# ATMega32U4.net
KiCad netlist of a schematic drawn in Altium Designer
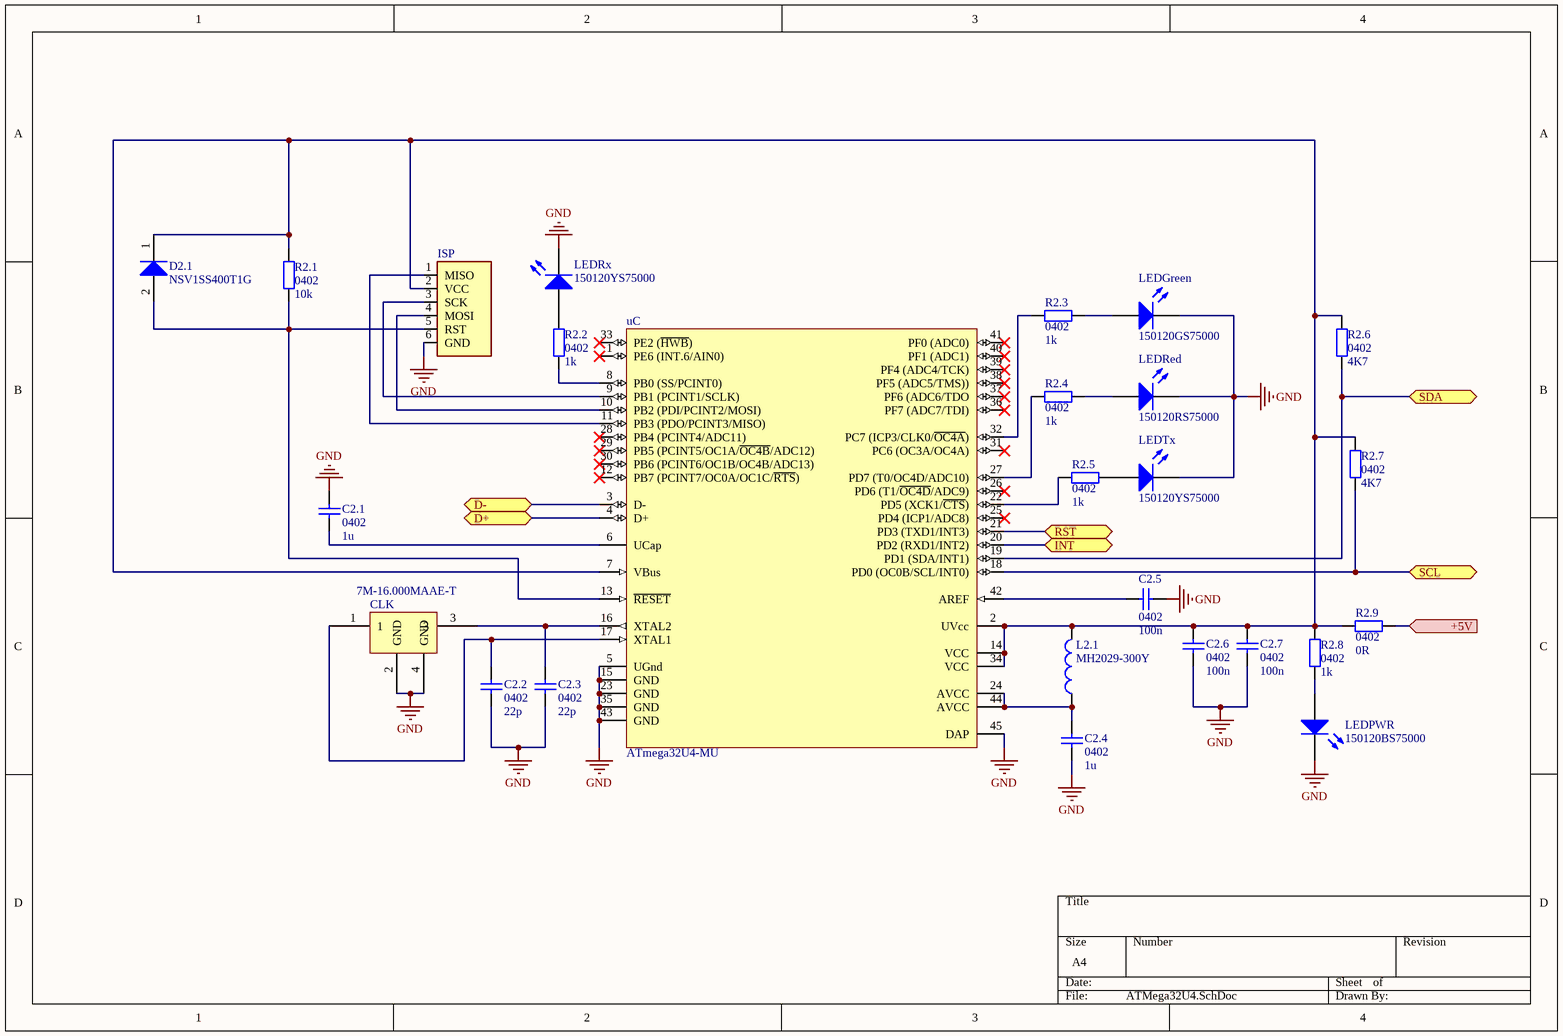
[diagram p0: ATMega32U4.SchDoc]

(export (version "E")
  (design (tool "Eeschema 10.0.6"))
  (components
    (comp (ref "C2.1")
      (value "0402")
      (footprint "C0402_M")
      (description "Capacitor")
      (fields
        (field (name "PART NUMBER") "C0402_X5R_1u_10V_WE")
        (field (name "ALTIUM_VALUE") "1u")
        (field (name "TOLERANCE") "±20%")
      )
      (libsource (lib "LTE_altium") (part "Cap"))
    )
    (comp (ref "C2.2")
      (value "0402")
      (footprint "C0402_M")
      (description "Capacitor")
      (fields
        (field (name "PART NUMBER") "C0402_NP0_22p_50V_WE")
        (field (name "ALTIUM_VALUE") "22p")
        (field (name "TOLERANCE") "±5%")
      )
      (libsource (lib "LTE_altium") (part "Cap"))
    )
    (comp (ref "C2.3")
      (value "0402")
      (footprint "C0402_M")
      (description "Capacitor")
      (fields
        (field (name "PART NUMBER") "C0402_NP0_22p_50V_WE")
        (field (name "ALTIUM_VALUE") "22p")
        (field (name "TOLERANCE") "±5%")
      )
      (libsource (lib "LTE_altium") (part "Cap"))
    )
    (comp (ref "C2.4")
      (value "0402")
      (footprint "C0402_M")
      (description "Capacitor")
      (fields
        (field (name "PART NUMBER") "C0402_X5R_1u_10V_WE")
        (field (name "ALTIUM_VALUE") "1u")
        (field (name "TOLERANCE") "±20%")
      )
      (libsource (lib "LTE_altium") (part "Cap"))
    )
    (comp (ref "C2.5")
      (value "0402")
      (footprint "C0402_M")
      (description "Capacitor")
      (fields
        (field (name "PART NUMBER") "C0402_X7R_100n_10%")
        (field (name "ALTIUM_VALUE") "100n")
        (field (name "TOLERANCE") "10%")
      )
      (libsource (lib "LTE_altium") (part "Cap"))
    )
    (comp (ref "C2.6")
      (value "0402")
      (footprint "C0402_M")
      (description "Capacitor")
      (fields
        (field (name "PART NUMBER") "C0402_X7R_100n_10%")
        (field (name "ALTIUM_VALUE") "100n")
        (field (name "TOLERANCE") "10%")
      )
      (libsource (lib "LTE_altium") (part "Cap"))
    )
    (comp (ref "C2.7")
      (value "0402")
      (footprint "C0402_M")
      (description "Capacitor")
      (fields
        (field (name "PART NUMBER") "C0402_X7R_100n_10%")
        (field (name "ALTIUM_VALUE") "100n")
        (field (name "TOLERANCE") "10%")
      )
      (libsource (lib "LTE_altium") (part "Cap"))
    )
    (comp (ref "CLK")
      (value "7M-16.000MAAE-T")
      (footprint "7M-16.000MAAE-T")
      (libsource (lib "7M-16.000MAAE-T") (part "7M-16.000MAAE-T"))
    )
    (comp (ref "D2.1")
      (value "NSV1SS400T1G")
      (footprint "ONSC-SOD-523-2-502-01_V")
      (description "High-Speed Switching Diode, 2-Pin SOD-523, Pb-Free, Tape and Reel")
      (fields (field (name "MANUFACTURER") "On Semiconductor"))
      (libsource (lib "Altium Content Vault") (part "ONSC-D-K1A2-2"))
    )
    (comp (ref "ISP")
      (value "~")
      (footprint "TAG_TC2030-IDC-NL")
      (description "6-PIN PLUG-OF-NAILS CABLE 6")
      (fields (field (name "MF") "Tag-Connect") (field (name "MP") "TC2030-IDC-NL"))
      (libsource (lib "TC2030") (part "TC2030-IDC-NL"))
    )
    (comp (ref "L2.1")
      (value "MH2029-300Y")
      (footprint "L0805_M")
      (fields
        (field (name "PART NUMBER") "L0805_100n_2%")
        (field (name "TOLERANCE") "2%")
        (field (name "MANUFACTORPARTNUMBER") "0805CS-101XJLC")
      )
      (libsource (lib "LTE_altium") (part "Inductor"))
    )
    (comp (ref "LEDGreen")
      (value "150120GS75000")
      (footprint "1206_A")
      (description "SMD mono-color Chip LED, WL-SMCW, Green")
      (fields (field (name "MANUFACTURER") "Wuerth Elektronik"))
      (libsource (lib "Altium Content Vault") (part "WE-LED_K1A2-2"))
    )
    (comp (ref "LEDPWR")
      (value "150120BS75000")
      (footprint "1206_A")
      (description "SMD mono-color Chip LED, WL-SMCW, Blue")
      (fields (field (name "MANUFACTURER") "Wuerth Elektronik"))
      (libsource (lib "Altium Content Vault") (part "WE-LED_K1A2-2"))
    )
    (comp (ref "LEDRed")
      (value "150120RS75000")
      (footprint "1206_A")
      (description "SMD mono-color Chip LED, WL-SMCW, Red")
      (fields (field (name "MANUFACTURER") "Wuerth Elektronik"))
      (libsource (lib "Altium Content Vault") (part "WE-LED_K1A2-2"))
    )
    (comp (ref "LEDRx")
      (value "150120YS75000")
      (footprint "1206_A")
      (description "SMD mono-color Chip LED, WL-SMCW, Yellow")
      (fields (field (name "MANUFACTURER") "Wuerth Elektronik"))
      (libsource (lib "Altium Content Vault") (part "WE-LED_K1A2-2"))
    )
    (comp (ref "LEDTx")
      (value "150120YS75000")
      (footprint "1206_A")
      (description "SMD mono-color Chip LED, WL-SMCW, Yellow")
      (fields (field (name "MANUFACTURER") "Wuerth Elektronik"))
      (libsource (lib "Altium Content Vault") (part "WE-LED_K1A2-2"))
    )
    (comp (ref "R2.1")
      (value "0402")
      (footprint "R0402_M")
      (description "Resistor")
      (fields
        (field (name "PART NUMBER") "R0402_1%_10k")
        (field (name "ALTIUM_VALUE") "10k")
        (field (name "TOLERANCE") "1%")
      )
      (libsource (lib "LTE_altium") (part "Res"))
    )
    (comp (ref "R2.2")
      (value "0402")
      (footprint "R0402_M")
      (description "Resistor")
      (fields
        (field (name "PART NUMBER") "R0402_1%_1k")
        (field (name "ALTIUM_VALUE") "1k")
        (field (name "TOLERANCE") "1%")
      )
      (libsource (lib "LTE_altium") (part "Res"))
    )
    (comp (ref "R2.3")
      (value "0402")
      (footprint "R0402_M")
      (description "Resistor")
      (fields
        (field (name "PART NUMBER") "R0402_1%_1k")
        (field (name "ALTIUM_VALUE") "1k")
        (field (name "TOLERANCE") "1%")
      )
      (libsource (lib "") (part "Res_1"))
    )
    (comp (ref "R2.4")
      (value "0402")
      (footprint "R0402_M")
      (description "Resistor")
      (fields
        (field (name "PART NUMBER") "R0402_1%_1k")
        (field (name "ALTIUM_VALUE") "1k")
        (field (name "TOLERANCE") "1%")
      )
      (libsource (lib "") (part "Res_1"))
    )
    (comp (ref "R2.5")
      (value "0402")
      (footprint "R0402_M")
      (description "Resistor")
      (fields
        (field (name "PART NUMBER") "R0402_1%_1k")
        (field (name "ALTIUM_VALUE") "1k")
        (field (name "TOLERANCE") "1%")
      )
      (libsource (lib "") (part "Res_1"))
    )
    (comp (ref "R2.6")
      (value "0402")
      (footprint "R0402_M")
      (description "Resistor")
      (fields
        (field (name "PART NUMBER") "R0402_1%_3k3")
        (field (name "ALTIUM_VALUE") "4K7")
        (field (name "TOLERANCE") "1%")
      )
      (libsource (lib "LTE_altium") (part "Res"))
    )
    (comp (ref "R2.7")
      (value "0402")
      (footprint "R0402_M")
      (description "Resistor")
      (fields
        (field (name "PART NUMBER") "R0402_1%_3k3")
        (field (name "ALTIUM_VALUE") "4K7")
        (field (name "TOLERANCE") "1%")
      )
      (libsource (lib "LTE_altium") (part "Res"))
    )
    (comp (ref "R2.8")
      (value "0402")
      (footprint "R0402_M")
      (description "Resistor")
      (fields
        (field (name "PART NUMBER") "R0402_1%_1k")
        (field (name "ALTIUM_VALUE") "1k")
        (field (name "TOLERANCE") "1%")
      )
      (libsource (lib "LTE_altium") (part "Res"))
    )
    (comp (ref "R2.9")
      (value "0402")
      (footprint "R0402_M")
      (description "Resistor")
      (fields
        (field (name "PART NUMBER") "R0402_1%_0R")
        (field (name "ALTIUM_VALUE") "0R")
        (field (name "TOLERANCE") "1%")
      )
      (libsource (lib "") (part "Res_2"))
    )
    (comp (ref "uC")
      (value "ATmega32U4-MU")
      (footprint "44PW_M")
      (libsource (lib "Altium Content Vault") (part "MC-8B-ATM16U4-SQ45"))
    )
  )
  (nets
    (net (code "1") (name "/+5V") (class "Default")
      (node (ref "R2.9") (pin "2") (pinfunction "2_2") (pintype "passive"))
    )
    (net (code "2") (name "/D+") (class "Default")
      (node (ref "uC") (pin "4") (pinfunction "D+_4") (pintype "bidirectional"))
    )
    (net (code "3") (name "/D-") (class "Default")
      (node (ref "uC") (pin "3") (pinfunction "D-_3") (pintype "bidirectional"))
    )
    (net (code "4") (name "/INT") (class "Default")
      (node (ref "uC") (pin "20") (pinfunction "PD2_(RXD1/INT2)_20") (pintype "bidirectional"))
    )
    (net (code "5") (name "/RST") (class "Default")
      (node (ref "uC") (pin "21") (pinfunction "PD3_(TXD1/INT3)_21") (pintype "bidirectional"))
    )
    (net (code "6") (name "/SCL") (class "Default")
      (node (ref "R2.7") (pin "1") (pinfunction "1_1") (pintype "passive"))
      (node (ref "uC") (pin "18") (pinfunction "PD0_(OC0B/SCL/INT0)_18") (pintype "bidirectional"))
    )
    (net (code "7") (name "/SDA") (class "Default")
      (node (ref "R2.6") (pin "1") (pinfunction "1_1") (pintype "passive"))
      (node (ref "uC") (pin "19") (pinfunction "PD1_(SDA/INT1)_19") (pintype "bidirectional"))
    )
    (net (code "8") (name "GND") (class "Default")
      (node (ref "C2.1") (pin "2") (pinfunction "2_2") (pintype "passive"))
      (node (ref "C2.2") (pin "1") (pinfunction "1_1") (pintype "passive"))
      (node (ref "C2.3") (pin "1") (pinfunction "1_1") (pintype "passive"))
      (node (ref "C2.4") (pin "1") (pinfunction "1_1") (pintype "passive"))
      (node (ref "C2.5") (pin "2") (pinfunction "2_2") (pintype "passive"))
      (node (ref "C2.6") (pin "1") (pinfunction "1_1") (pintype "passive"))
      (node (ref "C2.7") (pin "1") (pinfunction "1_1") (pintype "passive"))
      (node (ref "CLK") (pin "2") (pinfunction "GND_2") (pintype "passive"))
      (node (ref "CLK") (pin "4") (pinfunction "GND_4") (pintype "passive"))
      (node (ref "ISP") (pin "6") (pinfunction "GND_6") (pintype "passive"))
      (node (ref "LEDGreen") (pin "1") (pinfunction "K_1") (pintype "passive"))
      (node (ref "LEDPWR") (pin "1") (pinfunction "K_1") (pintype "passive"))
      (node (ref "LEDRed") (pin "1") (pinfunction "K_1") (pintype "passive"))
      (node (ref "LEDRx") (pin "1") (pinfunction "K_1") (pintype "passive"))
      (node (ref "LEDTx") (pin "1") (pinfunction "K_1") (pintype "passive"))
      (node (ref "uC") (pin "15") (pinfunction "GND_15") (pintype "power_in"))
      (node (ref "uC") (pin "23") (pinfunction "GND_23") (pintype "power_in"))
      (node (ref "uC") (pin "35") (pinfunction "GND_35") (pintype "power_in"))
      (node (ref "uC") (pin "43") (pinfunction "GND_43") (pintype "power_in"))
      (node (ref "uC") (pin "45") (pinfunction "DAP_45") (pintype "power_in"))
      (node (ref "uC") (pin "5") (pinfunction "UGnd_5") (pintype "power_in"))
    )
    (net (code "9") (name "Net-(C2.4-Pad2)") (class "Default")
      (node (ref "C2.4") (pin "2") (pinfunction "2_2") (pintype "passive"))
      (node (ref "L2.1") (pin "1") (pinfunction "1_1") (pintype "passive"))
      (node (ref "uC") (pin "24") (pinfunction "AVCC_24") (pintype "power_in"))
      (node (ref "uC") (pin "44") (pinfunction "AVCC_44") (pintype "power_in"))
    )
    (net (code "10") (name "Net-(D2.1-A)") (class "Default")
      (node (ref "D2.1") (pin "2") (pinfunction "A_2") (pintype "passive"))
      (node (ref "ISP") (pin "5") (pinfunction "RST_5") (pintype "passive"))
      (node (ref "R2.1") (pin "1") (pinfunction "1_1") (pintype "passive"))
      (node (ref "uC") (pin "13") (pinfunction "~{RESET}_13") (pintype "input"))
    )
    (net (code "11") (name "Net-(D2.1-K)") (class "Default")
      (node (ref "C2.6") (pin "2") (pinfunction "2_2") (pintype "passive"))
      (node (ref "C2.7") (pin "2") (pinfunction "2_2") (pintype "passive"))
      (node (ref "D2.1") (pin "1") (pinfunction "K_1") (pintype "passive"))
      (node (ref "ISP") (pin "2") (pinfunction "VCC_2") (pintype "passive"))
      (node (ref "L2.1") (pin "2") (pinfunction "2_2") (pintype "passive"))
      (node (ref "R2.1") (pin "2") (pinfunction "2_2") (pintype "passive"))
      (node (ref "R2.6") (pin "2") (pinfunction "2_2") (pintype "passive"))
      (node (ref "R2.7") (pin "2") (pinfunction "2_2") (pintype "passive"))
      (node (ref "R2.8") (pin "2") (pinfunction "2_2") (pintype "passive"))
      (node (ref "R2.9") (pin "1") (pinfunction "1_1") (pintype "passive"))
      (node (ref "uC") (pin "14") (pinfunction "VCC_14") (pintype "power_in"))
      (node (ref "uC") (pin "2") (pinfunction "UVcc_2") (pintype "power_in"))
      (node (ref "uC") (pin "34") (pinfunction "VCC_34") (pintype "power_in"))
      (node (ref "uC") (pin "7") (pinfunction "VBus_7") (pintype "input"))
    )
    (net (code "12") (name "Net-(ISP-MISO)") (class "Default")
      (node (ref "ISP") (pin "1") (pinfunction "MISO_1") (pintype "passive"))
      (node (ref "uC") (pin "11") (pinfunction "PB3_(PDO/PCINT3/MISO)_11") (pintype "bidirectional"))
    )
    (net (code "13") (name "Net-(ISP-MOSI)") (class "Default")
      (node (ref "ISP") (pin "4") (pinfunction "MOSI_4") (pintype "passive"))
      (node (ref "uC") (pin "10") (pinfunction "PB2_(PDI/PCINT2/MOSI)_10") (pintype "bidirectional"))
    )
    (net (code "14") (name "Net-(ISP-SCK)") (class "Default")
      (node (ref "ISP") (pin "3") (pinfunction "SCK_3") (pintype "passive"))
      (node (ref "uC") (pin "9") (pinfunction "PB1_(PCINT1/SCLK)_9") (pintype "bidirectional"))
    )
    (net (code "15") (name "Net-(LEDGreen-A)") (class "Default")
      (node (ref "LEDGreen") (pin "2") (pinfunction "A_2") (pintype "passive"))
      (node (ref "R2.3") (pin "1") (pinfunction "1_1") (pintype "passive"))
    )
    (net (code "16") (name "Net-(LEDPWR-A)") (class "Default")
      (node (ref "LEDPWR") (pin "2") (pinfunction "A_2") (pintype "passive"))
      (node (ref "R2.8") (pin "1") (pinfunction "1_1") (pintype "passive"))
    )
    (net (code "17") (name "Net-(LEDRed-A)") (class "Default")
      (node (ref "LEDRed") (pin "2") (pinfunction "A_2") (pintype "passive"))
      (node (ref "R2.4") (pin "1") (pinfunction "1_1") (pintype "passive"))
    )
    (net (code "18") (name "Net-(LEDRx-A)") (class "Default")
      (node (ref "LEDRx") (pin "2") (pinfunction "A_2") (pintype "passive"))
      (node (ref "R2.2") (pin "2") (pinfunction "2_2") (pintype "passive"))
    )
    (net (code "19") (name "Net-(LEDTx-A)") (class "Default")
      (node (ref "LEDTx") (pin "2") (pinfunction "A_2") (pintype "passive"))
      (node (ref "R2.5") (pin "1") (pinfunction "1_1") (pintype "passive"))
    )
    (net (code "20") (name "Net-(uC-AREF)") (class "Default")
      (node (ref "C2.5") (pin "1") (pinfunction "1_1") (pintype "passive"))
      (node (ref "uC") (pin "42") (pinfunction "AREF_42") (pintype "input"))
    )
    (net (code "21") (name "Net-(uC-PB0_(SS{slash}PCINT0))") (class "Default")
      (node (ref "R2.2") (pin "1") (pinfunction "1_1") (pintype "passive"))
      (node (ref "uC") (pin "8") (pinfunction "PB0_(SS/PCINT0)_8") (pintype "bidirectional"))
    )
    (net (code "22") (name "Net-(uC-PC7_(ICP3{slash}CLK0{slash}~{OC4A}))") (class "Default")
      (node (ref "R2.3") (pin "2") (pinfunction "2_2") (pintype "passive"))
      (node (ref "uC") (pin "32") (pinfunction "PC7_(ICP3/CLK0/~{OC4A})_32") (pintype "bidirectional"))
    )
    (net (code "23") (name "Net-(uC-PD5_(XCK1{slash}~{CTS}))") (class "Default")
      (node (ref "R2.5") (pin "2") (pinfunction "2_2") (pintype "passive"))
      (node (ref "uC") (pin "22") (pinfunction "PD5_(XCK1/~{CTS})_22") (pintype "bidirectional"))
    )
    (net (code "24") (name "Net-(uC-PD7_(T0{slash}OC4D{slash}ADC10))") (class "Default")
      (node (ref "R2.4") (pin "2") (pinfunction "2_2") (pintype "passive"))
      (node (ref "uC") (pin "27") (pinfunction "PD7_(T0/OC4D/ADC10)_27") (pintype "bidirectional"))
    )
    (net (code "25") (name "Net-(uC-UCap)") (class "Default")
      (node (ref "C2.1") (pin "1") (pinfunction "1_1") (pintype "passive"))
      (node (ref "uC") (pin "6") (pinfunction "UCap_6") (pintype "passive"))
    )
    (net (code "26") (name "Net-(uC-XTAL1)") (class "Default")
      (node (ref "C2.2") (pin "2") (pinfunction "2_2") (pintype "passive"))
      (node (ref "CLK") (pin "1") (pinfunction "1_1") (pintype "passive"))
      (node (ref "uC") (pin "17") (pinfunction "XTAL1_17") (pintype "input"))
    )
    (net (code "27") (name "Net-(uC-XTAL2)") (class "Default")
      (node (ref "C2.3") (pin "2") (pinfunction "2_2") (pintype "passive"))
      (node (ref "CLK") (pin "3") (pinfunction "3_3") (pintype "passive"))
      (node (ref "uC") (pin "16") (pinfunction "XTAL2_16") (pintype "output"))
    )
    (net (code "28") (name "unconnected-(uC-PB4_(PCINT4{slash}ADC11)-Pad28)") (class "Default")
      (node (ref "uC") (pin "28") (pinfunction "PB4_(PCINT4/ADC11)_28") (pintype "bidirectional+no_connect"))
    )
    (net (code "29") (name "unconnected-(uC-PB5_(PCINT5{slash}OC1A{slash}~{OC4B}{slash}ADC12)-Pad29)") (class "Default")
      (node (ref "uC") (pin "29") (pinfunction "PB5_(PCINT5/OC1A/~{OC4B}/ADC12)_29") (pintype "bidirectional+no_connect"))
    )
    (net (code "30") (name "unconnected-(uC-PB6_(PCINT6{slash}OC1B{slash}OC4B{slash}ADC13)-Pad30)") (class "Default")
      (node (ref "uC") (pin "30") (pinfunction "PB6_(PCINT6/OC1B/OC4B/ADC13)_30") (pintype "bidirectional+no_connect"))
    )
    (net (code "31") (name "unconnected-(uC-PB7_(PCINT7{slash}OC0A{slash}OC1C{slash}~{RTS})-Pad12)") (class "Default")
      (node (ref "uC") (pin "12") (pinfunction "PB7_(PCINT7/OC0A/OC1C/~{RTS})_12") (pintype "bidirectional+no_connect"))
    )
    (net (code "32") (name "unconnected-(uC-PC6_(OC3A{slash}OC4A)-Pad31)") (class "Default")
      (node (ref "uC") (pin "31") (pinfunction "PC6_(OC3A/OC4A)_31") (pintype "bidirectional+no_connect"))
    )
    (net (code "33") (name "unconnected-(uC-PD4_(ICP1{slash}ADC8)-Pad25)") (class "Default")
      (node (ref "uC") (pin "25") (pinfunction "PD4_(ICP1/ADC8)_25") (pintype "bidirectional+no_connect"))
    )
    (net (code "34") (name "unconnected-(uC-PD6_(T1{slash}~{OC4D}{slash}ADC9)-Pad26)") (class "Default")
      (node (ref "uC") (pin "26") (pinfunction "PD6_(T1/~{OC4D}/ADC9)_26") (pintype "bidirectional+no_connect"))
    )
    (net (code "35") (name "unconnected-(uC-PE2_(~{HWB})-Pad33)") (class "Default")
      (node (ref "uC") (pin "33") (pinfunction "PE2_(~{HWB})_33") (pintype "bidirectional+no_connect"))
    )
    (net (code "36") (name "unconnected-(uC-PE6_(INT.6{slash}AIN0)-Pad1)") (class "Default")
      (node (ref "uC") (pin "1") (pinfunction "PE6_(INT.6/AIN0)_1") (pintype "bidirectional+no_connect"))
    )
    (net (code "37") (name "unconnected-(uC-PF0_(ADC0)-Pad41)") (class "Default")
      (node (ref "uC") (pin "41") (pinfunction "PF0_(ADC0)_41") (pintype "bidirectional+no_connect"))
    )
    (net (code "38") (name "unconnected-(uC-PF1_(ADC1)-Pad40)") (class "Default")
      (node (ref "uC") (pin "40") (pinfunction "PF1_(ADC1)_40") (pintype "bidirectional+no_connect"))
    )
    (net (code "39") (name "unconnected-(uC-PF4_(ADC4{slash}TCK)-Pad39)") (class "Default")
      (node (ref "uC") (pin "39") (pinfunction "PF4_(ADC4/TCK)_39") (pintype "bidirectional+no_connect"))
    )
    (net (code "40") (name "unconnected-(uC-PF5_(ADC5{slash}TMS))-Pad38)") (class "Default")
      (node (ref "uC") (pin "38") (pinfunction "PF5_(ADC5/TMS))_38") (pintype "bidirectional+no_connect"))
    )
    (net (code "41") (name "unconnected-(uC-PF6_(ADC6{slash}TDO-Pad37)") (class "Default")
      (node (ref "uC") (pin "37") (pinfunction "PF6_(ADC6/TDO_37") (pintype "bidirectional+no_connect"))
    )
    (net (code "42") (name "unconnected-(uC-PF7_(ADC7{slash}TDI)-Pad36)") (class "Default")
      (node (ref "uC") (pin "36") (pinfunction "PF7_(ADC7/TDI)_36") (pintype "bidirectional+no_connect"))
    )
  )
)
